# VISION_BETA_EBB.net
KiCad netlist of a schematic drawn in Altium Designer
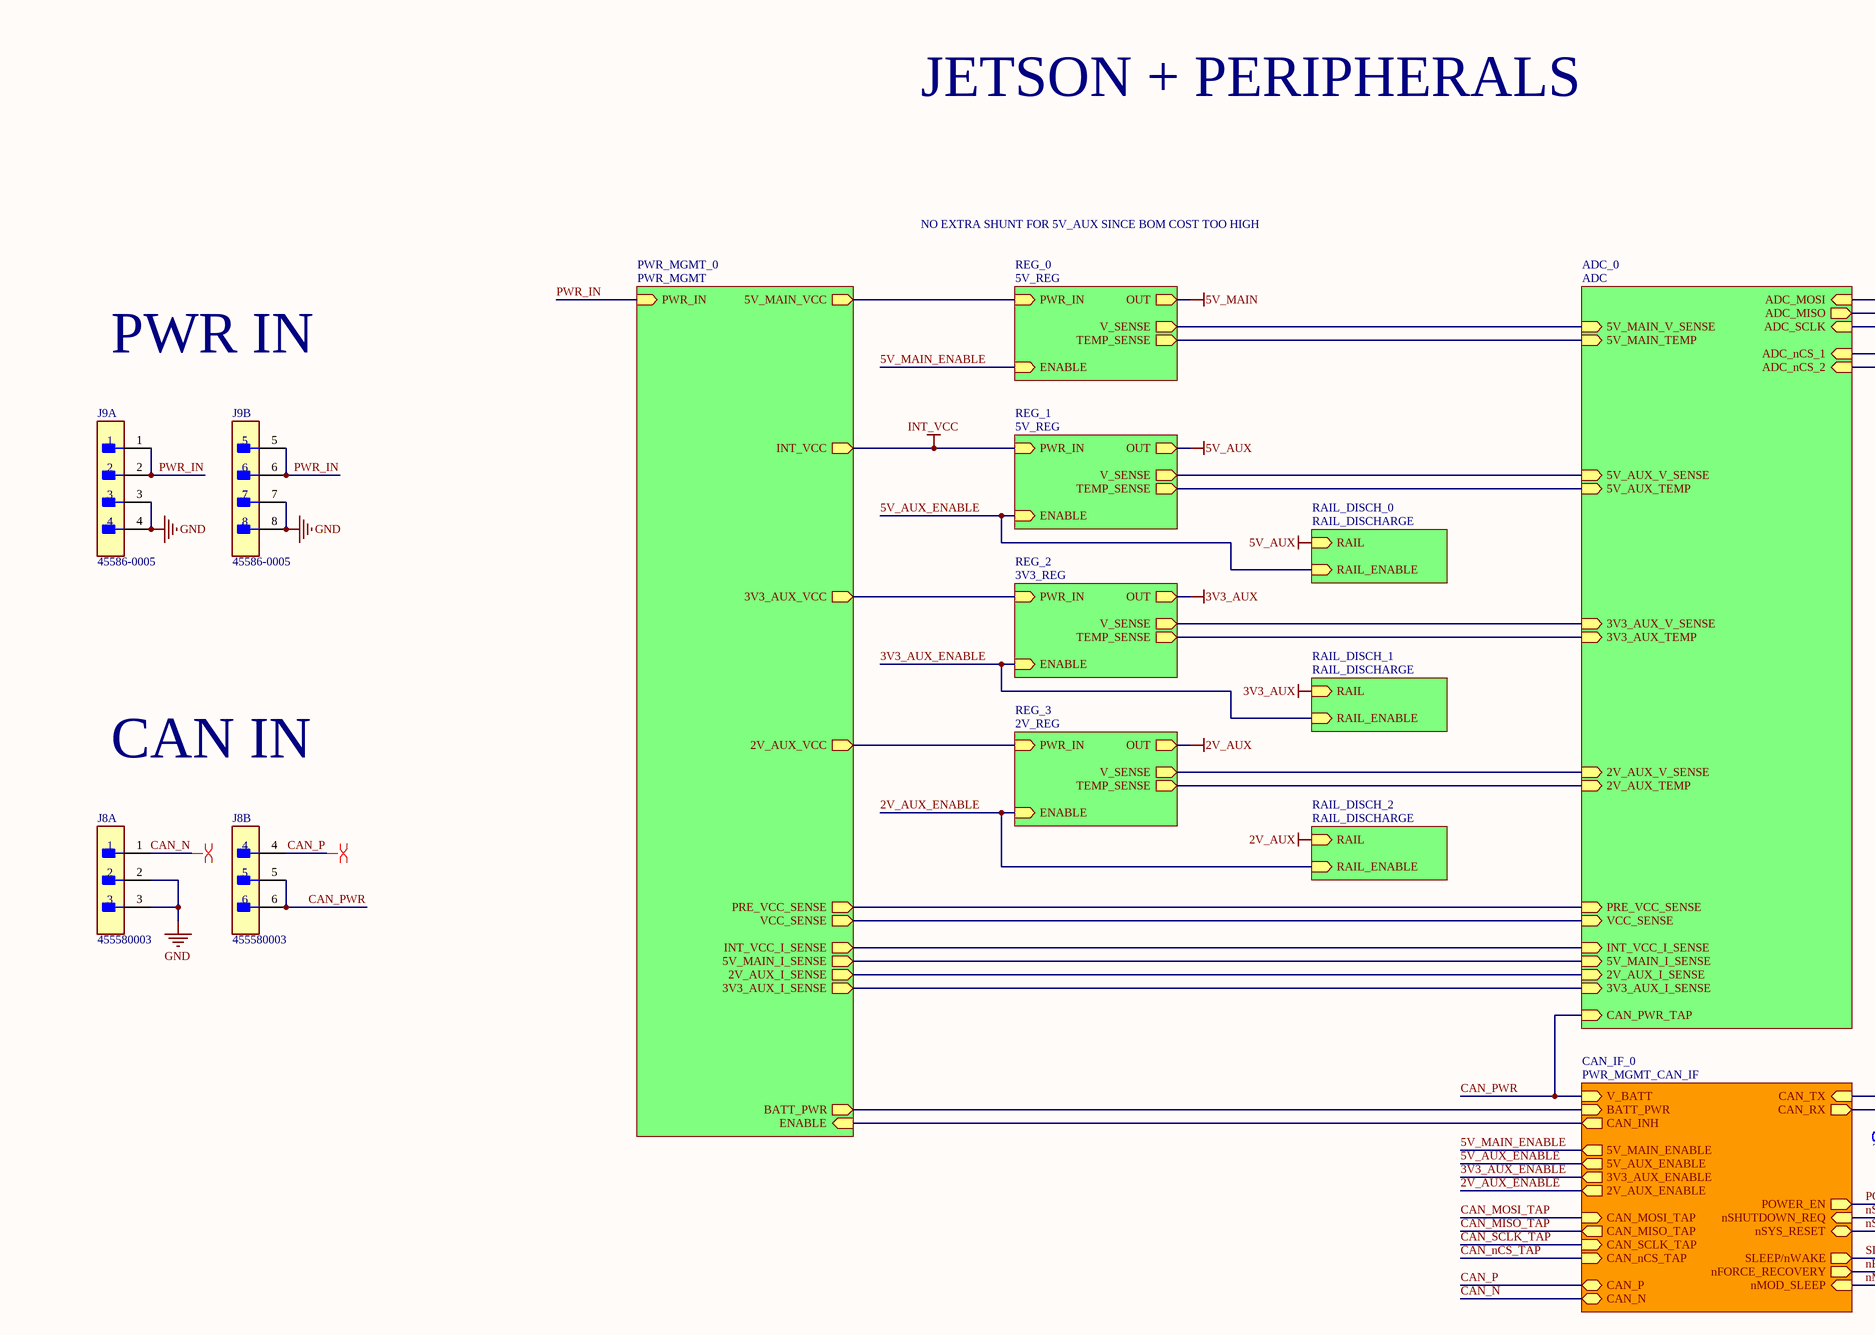
[diagram p0: VISION_BETA_EBB.SchDoc, top middle]
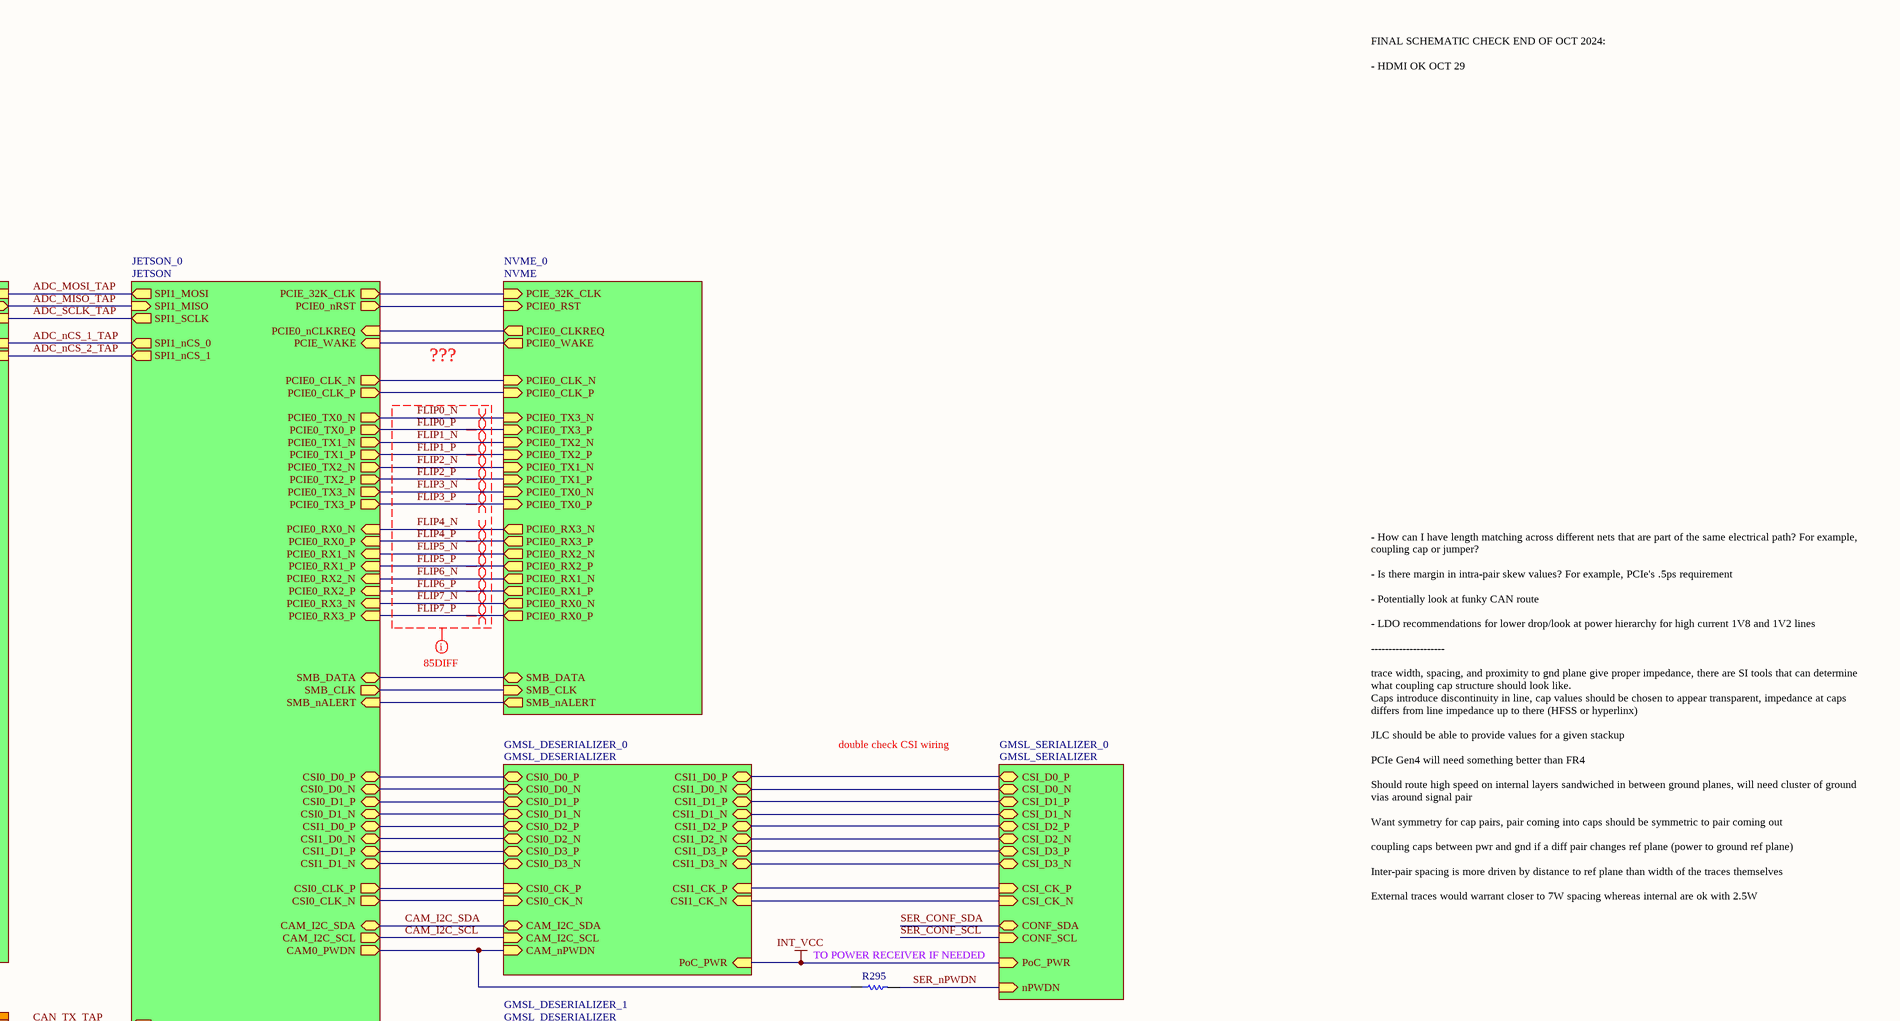
[diagram p1: VISION_BETA_EBB.SchDoc, top right]
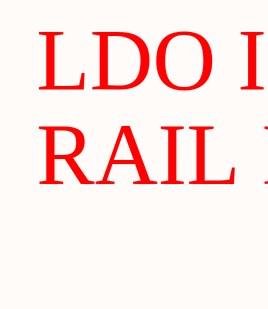
[diagram p2: VISION_BETA_EBB.SchDoc, bottom left]
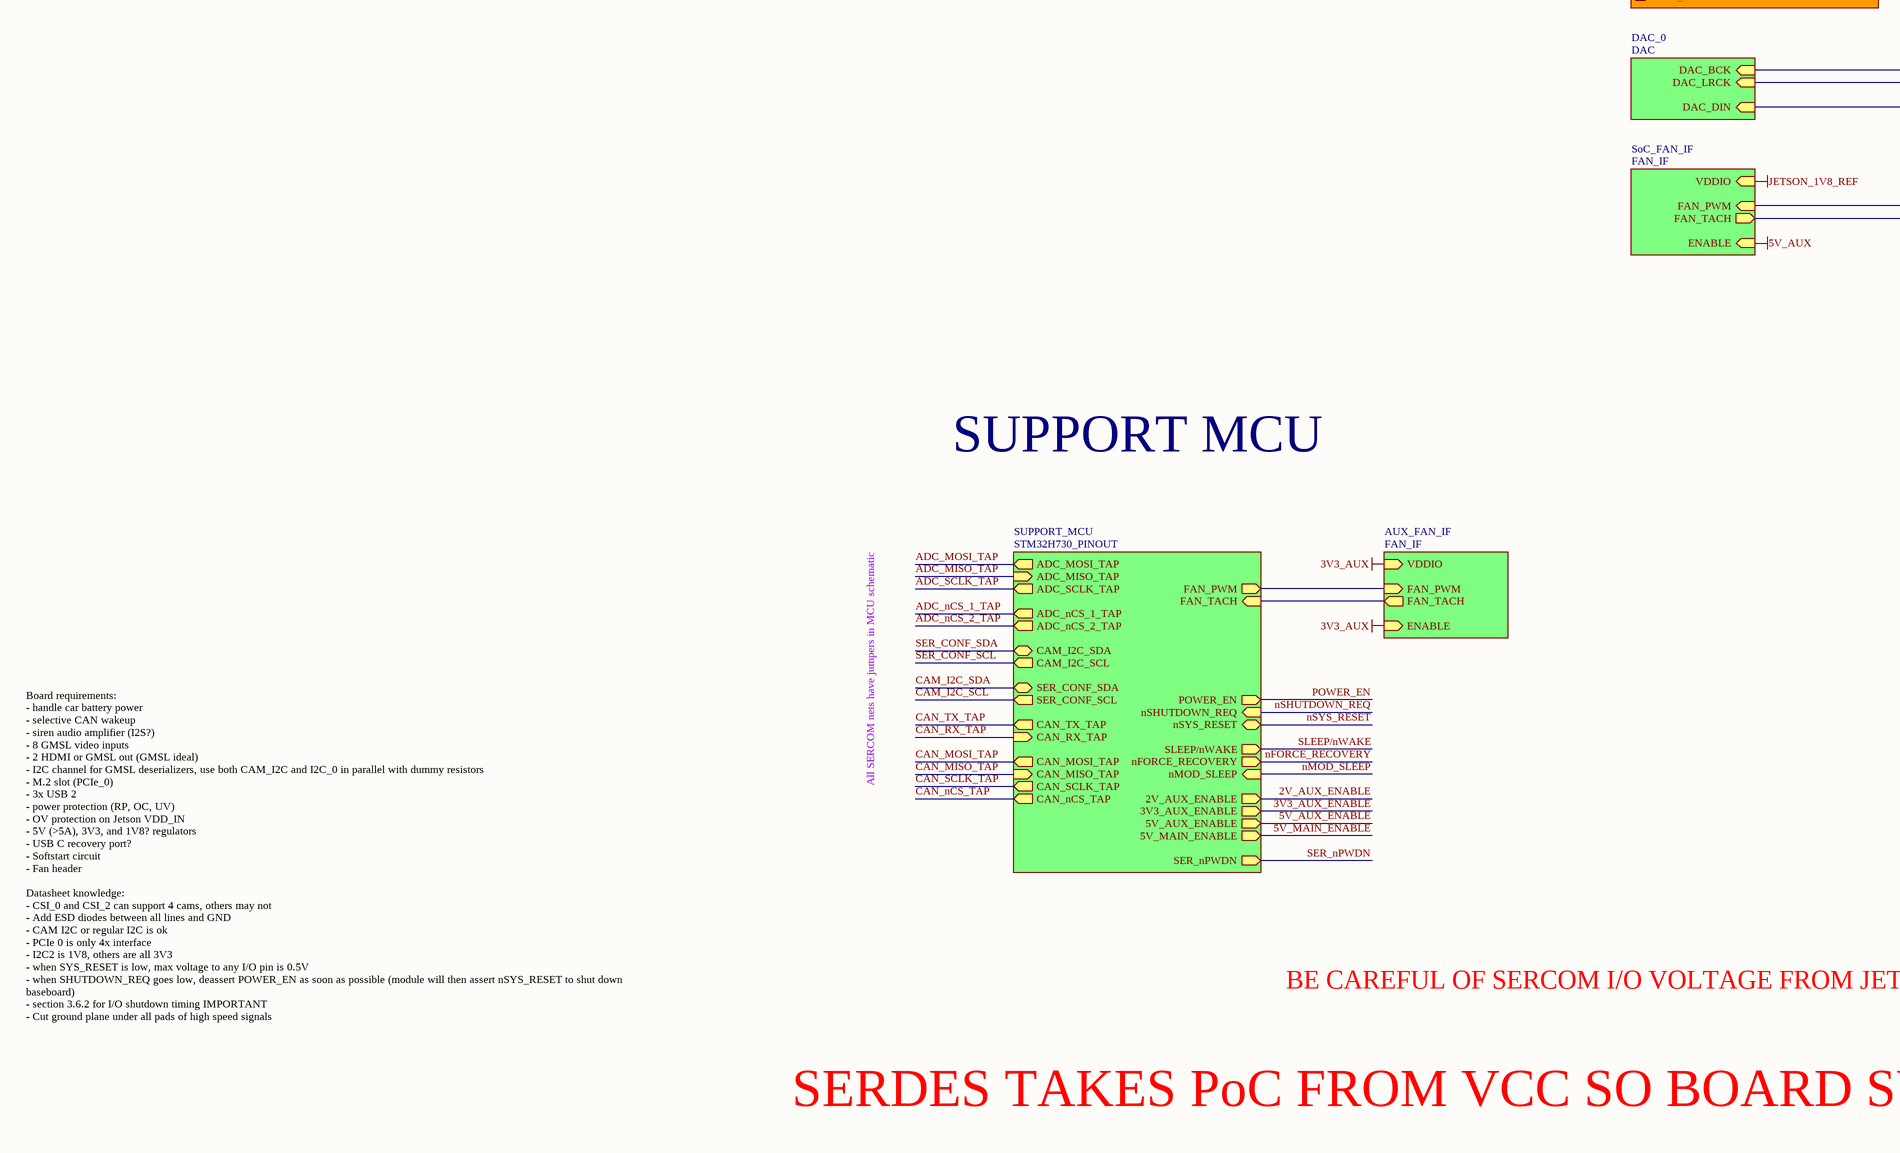
[diagram p3: VISION_BETA_EBB.SchDoc, bottom middle]
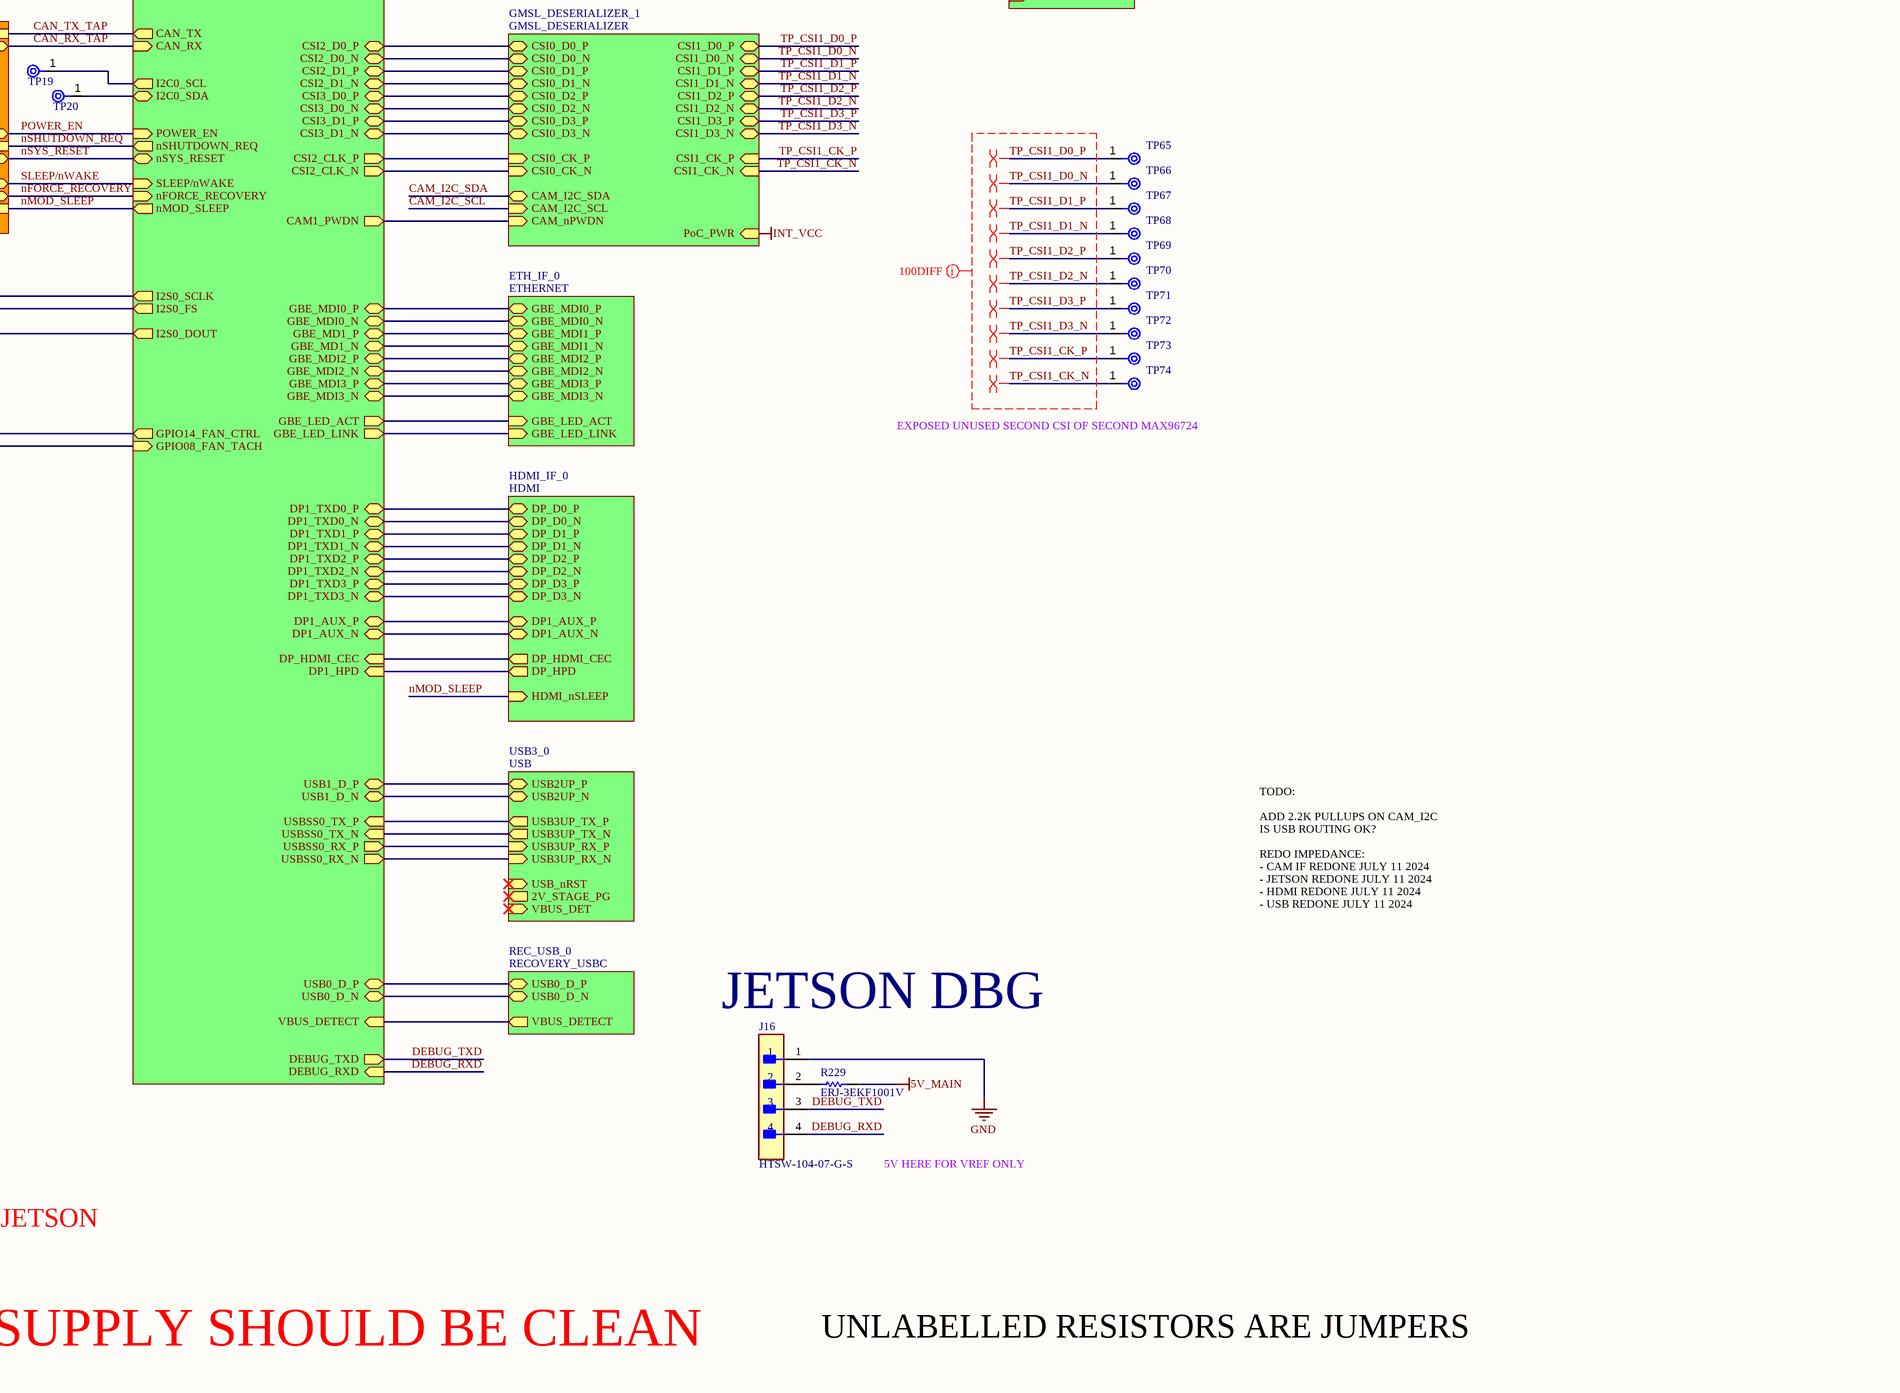
[diagram p4: VISION_BETA_EBB.SchDoc, bottom right]

(export (version "E")
  (design (tool "Eeschema 10.0.6"))
  (components
    (comp (ref "J8")
      (value "455580003")
      (footprint "FP-455580003-MFG")
      (description "CONN HEADER R/A 6POS 4.2MM")
      (fields
        (field (name "OCTOPART") "https://octopart.com/45558-0003-molex-7672845")
        (field (name "MANUFACTURER") "Molex")
      )
      (libsource (lib "Altium Content Vault") (part "bb9cbdb24149a20ba329b4e86909569"))
    )
    (comp (ref "J9")
      (value "45586-0005")
      (footprint "FP-45586-0005-MFG")
      (description "CONN HEADER R/A 8POS 4.2MM")
      (libsource (lib "Altium Content Vault") (part "85438c39ca9ef07d43bb2e97c52bc44"))
    )
    (comp (ref "J16")
      (value "HTSW-104-07-G-S")
      (footprint "FP-HTSW-104-07-G-S-MFG")
      (description "CONN HEADER VERT 4POS 2.54MM")
      (libsource (lib "Altium Content Vault") (part "299a8cea1bdcbc3624fe62c390fa72c"))
    )
    (comp (ref "R229")
      (value "ERJ-3EKF1001V")
      (footprint "RESC1608X55X30LL15T15")
      (fields (field (name "MANUFACTURER") "Panasonic"))
      (libsource (lib "Altium Content Vault") (part "RES"))
    )
    (comp (ref "R295")
      (value "0402 JUMPER")
      (footprint "RESC1005X40X25ML05T05")
      (description "READ THE NAME")
      (libsource (lib "Space Concordia") (part "CMP-009-00206-2"))
    )
    (comp (ref "TP19")
      (value "TPAD6R")
      (footprint "New footprint 1")
      (description "Test Point .6mm")
      (libsource (lib "Space Concordia") (part "TP"))
    )
    (comp (ref "TP20")
      (value "TPAD6R")
      (footprint "New footprint 1")
      (description "Test Point .6mm")
      (libsource (lib "Space Concordia") (part "TP"))
    )
    (comp (ref "TP65")
      (value "TPAD6R")
      (footprint "New footprint 1")
      (description "Test Point .6mm")
      (libsource (lib "Space Concordia") (part "TP"))
    )
    (comp (ref "TP66")
      (value "TPAD6R")
      (footprint "New footprint 1")
      (description "Test Point .6mm")
      (libsource (lib "Space Concordia") (part "TP"))
    )
    (comp (ref "TP67")
      (value "TPAD6R")
      (footprint "New footprint 1")
      (description "Test Point .6mm")
      (libsource (lib "Space Concordia") (part "TP"))
    )
    (comp (ref "TP68")
      (value "TPAD6R")
      (footprint "New footprint 1")
      (description "Test Point .6mm")
      (libsource (lib "Space Concordia") (part "TP"))
    )
    (comp (ref "TP69")
      (value "TPAD6R")
      (footprint "New footprint 1")
      (description "Test Point .6mm")
      (libsource (lib "Space Concordia") (part "TP"))
    )
    (comp (ref "TP70")
      (value "TPAD6R")
      (footprint "New footprint 1")
      (description "Test Point .6mm")
      (libsource (lib "Space Concordia") (part "TP"))
    )
    (comp (ref "TP71")
      (value "TPAD6R")
      (footprint "New footprint 1")
      (description "Test Point .6mm")
      (libsource (lib "Space Concordia") (part "TP"))
    )
    (comp (ref "TP72")
      (value "TPAD6R")
      (footprint "New footprint 1")
      (description "Test Point .6mm")
      (libsource (lib "Space Concordia") (part "TP"))
    )
    (comp (ref "TP73")
      (value "TPAD6R")
      (footprint "New footprint 1")
      (description "Test Point .6mm")
      (libsource (lib "Space Concordia") (part "TP"))
    )
    (comp (ref "TP74")
      (value "TPAD6R")
      (footprint "New footprint 1")
      (description "Test Point .6mm")
      (libsource (lib "Space Concordia") (part "TP"))
    )
  )
  (nets
    (net (code "18") (name "/CAM0_PWDN") (class "Default")
      (node (ref "R295") (pin "1") (pinfunction "1_1") (pintype "passive"))
    )
    (net (code "25") (name "/CAN_N") (class "Default")
      (node (ref "J8") (pin "1") (pinfunction "1_1") (pintype "passive"))
    )
    (net (code "26") (name "/CAN_P") (class "Default")
      (node (ref "J8") (pin "4") (pinfunction "4_4") (pintype "passive"))
    )
    (net (code "27") (name "/CAN_PWR") (class "Default")
      (node (ref "J8") (pin "5") (pinfunction "5_5") (pintype "passive"))
      (node (ref "J8") (pin "6") (pinfunction "6_6") (pintype "passive"))
    )
    (net (code "62") (name "/DEBUG_RXD") (class "Default")
      (node (ref "J16") (pin "4") (pinfunction "4_4") (pintype "passive"))
    )
    (net (code "63") (name "/DEBUG_TXD") (class "Default")
      (node (ref "J16") (pin "3") (pinfunction "3_3") (pintype "passive"))
    )
    (net (code "106") (name "/I2C0_SCL") (class "Default")
      (node (ref "TP19") (pin "1") (pinfunction "TP_1") (pintype "passive"))
    )
    (net (code "107") (name "/I2C0_SDA") (class "Default")
      (node (ref "TP20") (pin "1") (pinfunction "TP_1") (pintype "passive"))
    )
    (net (code "120") (name "/PWR_IN") (class "Default")
      (node (ref "J9") (pin "1") (pinfunction "1_1") (pintype "passive"))
      (node (ref "J9") (pin "2") (pinfunction "2_2") (pintype "passive"))
      (node (ref "J9") (pin "5") (pinfunction "5_5") (pintype "passive"))
      (node (ref "J9") (pin "6") (pinfunction "6_6") (pintype "passive"))
    )
    (net (code "123") (name "/SER_nPWDN") (class "Default")
      (node (ref "R295") (pin "2") (pinfunction "2_2") (pintype "passive"))
    )
    (net (code "132") (name "/TP_CSI1_CK_N") (class "Default")
      (node (ref "TP74") (pin "1") (pinfunction "TP_1") (pintype "passive"))
    )
    (net (code "133") (name "/TP_CSI1_CK_P") (class "Default")
      (node (ref "TP73") (pin "1") (pinfunction "TP_1") (pintype "passive"))
    )
    (net (code "134") (name "/TP_CSI1_D0_N") (class "Default")
      (node (ref "TP66") (pin "1") (pinfunction "TP_1") (pintype "passive"))
    )
    (net (code "135") (name "/TP_CSI1_D0_P") (class "Default")
      (node (ref "TP65") (pin "1") (pinfunction "TP_1") (pintype "passive"))
    )
    (net (code "136") (name "/TP_CSI1_D1_N") (class "Default")
      (node (ref "TP68") (pin "1") (pinfunction "TP_1") (pintype "passive"))
    )
    (net (code "137") (name "/TP_CSI1_D1_P") (class "Default")
      (node (ref "TP67") (pin "1") (pinfunction "TP_1") (pintype "passive"))
    )
    (net (code "138") (name "/TP_CSI1_D2_N") (class "Default")
      (node (ref "TP70") (pin "1") (pinfunction "TP_1") (pintype "passive"))
    )
    (net (code "139") (name "/TP_CSI1_D2_P") (class "Default")
      (node (ref "TP69") (pin "1") (pinfunction "TP_1") (pintype "passive"))
    )
    (net (code "140") (name "/TP_CSI1_D3_N") (class "Default")
      (node (ref "TP72") (pin "1") (pinfunction "TP_1") (pintype "passive"))
    )
    (net (code "141") (name "/TP_CSI1_D3_P") (class "Default")
      (node (ref "TP71") (pin "1") (pinfunction "TP_1") (pintype "passive"))
    )
    (net (code "165") (name "5V_MAIN") (class "Default")
      (node (ref "R229") (pin "1") (pinfunction "1_1") (pintype "passive"))
    )
    (net (code "166") (name "GND") (class "Default")
      (node (ref "J16") (pin "1") (pinfunction "1_1") (pintype "passive"))
      (node (ref "J8") (pin "2") (pinfunction "2_2") (pintype "passive"))
      (node (ref "J8") (pin "3") (pinfunction "3_3") (pintype "passive"))
      (node (ref "J9") (pin "3") (pinfunction "3_3") (pintype "passive"))
      (node (ref "J9") (pin "4") (pinfunction "4_4") (pintype "passive"))
      (node (ref "J9") (pin "7") (pinfunction "7_7") (pintype "passive"))
      (node (ref "J9") (pin "8") (pinfunction "8_8") (pintype "passive"))
    )
    (net (code "169") (name "Net-(J16-Pad2)") (class "Default")
      (node (ref "J16") (pin "2") (pinfunction "2_2") (pintype "passive"))
      (node (ref "R229") (pin "2") (pinfunction "2_2") (pintype "passive"))
    )
  )
)
